# PowerBord.net
KiCad netlist of a schematic drawn in Altium Designer
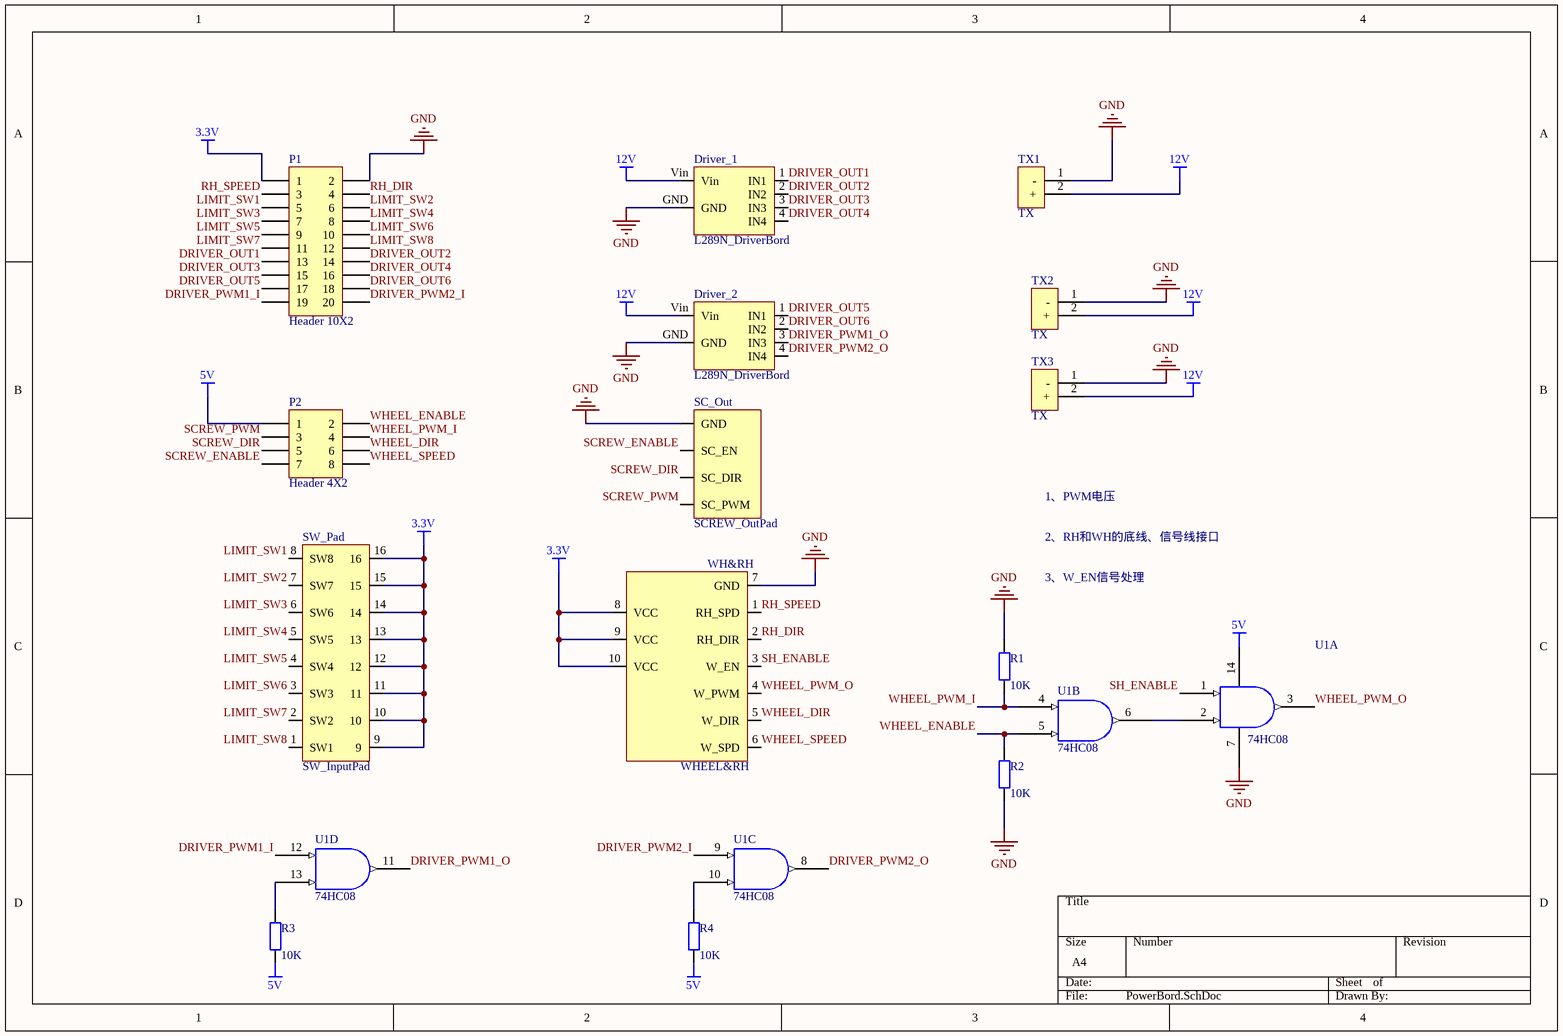
[diagram p0: PowerBord.SchDoc]

(export (version "E")
  (design (tool "Eeschema 10.0.6"))
  (components
    (comp (ref "Driver_1")
      (value "L289N_DriverBord")
      (footprint "L298N_DB")
      (libsource (lib "myLib") (part "L289N_DriverBord"))
    )
    (comp (ref "Driver_2")
      (value "L289N_DriverBord")
      (footprint "L298N_DB")
      (libsource (lib "myLib") (part "L289N_DriverBord"))
    )
    (comp (ref "P1")
      (value "Header 10X2")
      (footprint "JTAG20")
      (description "Header, 10-Pin, Dual row")
      (fields (field (name "PUBLISHER") "Altium Limited"))
      (libsource (lib "Miscellaneous Connectors") (part "Header 10X2"))
    )
    (comp (ref "P2")
      (value "Header 4X2")
      (footprint "HDR2X4")
      (description "Header, 4-Pin, Dual row")
      (fields (field (name "PUBLISHER") "Altium Limited"))
      (libsource (lib "Miscellaneous Connectors") (part "Header 4X2"))
    )
    (comp (ref "R1")
      (value "10K")
      (footprint "R 0805_M")
      (description "Resistor")
      (fields (field (name "PUBLISHER") "Altium Limited"))
      (libsource (lib "Miscellaneous Devices") (part "Res2"))
    )
    (comp (ref "R2")
      (value "10K")
      (footprint "R 0805_M")
      (description "Resistor")
      (fields (field (name "PUBLISHER") "Altium Limited"))
      (libsource (lib "Miscellaneous Devices") (part "Res2"))
    )
    (comp (ref "R3")
      (value "10K")
      (footprint "R 0805_M")
      (description "Resistor")
      (fields (field (name "PUBLISHER") "Altium Limited"))
      (libsource (lib "Miscellaneous Devices") (part "Res2"))
    )
    (comp (ref "R4")
      (value "10K")
      (footprint "R 0805_M")
      (description "Resistor")
      (fields (field (name "PUBLISHER") "Altium Limited"))
      (libsource (lib "Miscellaneous Devices") (part "Res2"))
    )
    (comp (ref "SC_Out")
      (value "SCREW_OutPad")
      (footprint "SC_OutPad")
      (libsource (lib "myLib") (part "SCREW_OutPad"))
    )
    (comp (ref "SW_Pad")
      (value "SW_InputPad")
      (footprint "SW_InputPad")
      (libsource (lib "myLib") (part "SW_InputPad"))
    )
    (comp (ref "TX1") (value "TX") (footprint "TX") (libsource (lib "接头") (part "T型插头")))
    (comp (ref "TX2") (value "TX") (footprint "TX") (libsource (lib "接头") (part "T型插头")))
    (comp (ref "TX3") (value "TX") (footprint "TX") (libsource (lib "接头") (part "T型插头")))
    (comp (ref "U1") (value "74HC08") (footprint "SOP-14") (libsource (lib "逻辑门器件") (part "74HC08")))
    (comp (ref "WH&RH") (value "WHEEL&RH") (footprint "WHEEL&RH") (libsource (lib "myLib") (part "WHEEL&RH")))
  )
  (nets
    (net (code "1") (name "/DRIVER_OUT1") (class "Default")
      (node (ref "Driver_1") (pin "1") (pinfunction "IN1_1") (pintype "passive"))
      (node (ref "P1") (pin "13") (pinfunction "13_13") (pintype "passive"))
    )
    (net (code "2") (name "/DRIVER_OUT2") (class "Default")
      (node (ref "Driver_1") (pin "2") (pinfunction "IN2_2") (pintype "passive"))
      (node (ref "P1") (pin "14") (pinfunction "14_14") (pintype "passive"))
    )
    (net (code "3") (name "/DRIVER_OUT3") (class "Default")
      (node (ref "Driver_1") (pin "3") (pinfunction "IN3_3") (pintype "passive"))
      (node (ref "P1") (pin "15") (pinfunction "15_15") (pintype "passive"))
    )
    (net (code "4") (name "/DRIVER_OUT4") (class "Default")
      (node (ref "Driver_1") (pin "4") (pinfunction "IN4_4") (pintype "passive"))
      (node (ref "P1") (pin "16") (pinfunction "16_16") (pintype "passive"))
    )
    (net (code "5") (name "/DRIVER_OUT5") (class "Default")
      (node (ref "Driver_2") (pin "1") (pinfunction "IN1_1") (pintype "passive"))
      (node (ref "P1") (pin "17") (pinfunction "17_17") (pintype "passive"))
    )
    (net (code "6") (name "/DRIVER_OUT6") (class "Default")
      (node (ref "Driver_2") (pin "2") (pinfunction "IN2_2") (pintype "passive"))
      (node (ref "P1") (pin "18") (pinfunction "18_18") (pintype "passive"))
    )
    (net (code "7") (name "/DRIVER_PWM1_I") (class "Default")
      (node (ref "P1") (pin "19") (pinfunction "19_19") (pintype "passive"))
      (node (ref "U1") (pin "12") (pintype "input"))
    )
    (net (code "8") (name "/DRIVER_PWM1_O") (class "Default")
      (node (ref "Driver_2") (pin "3") (pinfunction "IN3_3") (pintype "passive"))
      (node (ref "U1") (pin "11") (pintype "output"))
    )
    (net (code "9") (name "/DRIVER_PWM2_I") (class "Default")
      (node (ref "P1") (pin "20") (pinfunction "20_20") (pintype "passive"))
      (node (ref "U1") (pin "9") (pintype "input"))
    )
    (net (code "10") (name "/DRIVER_PWM2_O") (class "Default")
      (node (ref "Driver_2") (pin "4") (pinfunction "IN4_4") (pintype "passive"))
      (node (ref "U1") (pin "8") (pintype "output"))
    )
    (net (code "11") (name "/LIMIT_SW1") (class "Default")
      (node (ref "P1") (pin "5") (pinfunction "5_5") (pintype "passive"))
      (node (ref "SW_Pad") (pin "8") (pinfunction "SW8_8") (pintype "passive"))
    )
    (net (code "12") (name "/LIMIT_SW2") (class "Default")
      (node (ref "P1") (pin "6") (pinfunction "6_6") (pintype "passive"))
      (node (ref "SW_Pad") (pin "7") (pinfunction "SW7_7") (pintype "passive"))
    )
    (net (code "13") (name "/LIMIT_SW3") (class "Default")
      (node (ref "P1") (pin "7") (pinfunction "7_7") (pintype "passive"))
      (node (ref "SW_Pad") (pin "6") (pinfunction "SW6_6") (pintype "passive"))
    )
    (net (code "14") (name "/LIMIT_SW4") (class "Default")
      (node (ref "P1") (pin "8") (pinfunction "8_8") (pintype "passive"))
      (node (ref "SW_Pad") (pin "5") (pinfunction "SW5_5") (pintype "passive"))
    )
    (net (code "15") (name "/LIMIT_SW5") (class "Default")
      (node (ref "P1") (pin "9") (pinfunction "9_9") (pintype "passive"))
      (node (ref "SW_Pad") (pin "4") (pinfunction "SW4_4") (pintype "passive"))
    )
    (net (code "16") (name "/LIMIT_SW6") (class "Default")
      (node (ref "P1") (pin "10") (pinfunction "10_10") (pintype "passive"))
      (node (ref "SW_Pad") (pin "3") (pinfunction "SW3_3") (pintype "passive"))
    )
    (net (code "17") (name "/LIMIT_SW7") (class "Default")
      (node (ref "P1") (pin "11") (pinfunction "11_11") (pintype "passive"))
      (node (ref "SW_Pad") (pin "2") (pinfunction "SW2_2") (pintype "passive"))
    )
    (net (code "18") (name "/LIMIT_SW8") (class "Default")
      (node (ref "P1") (pin "12") (pinfunction "12_12") (pintype "passive"))
      (node (ref "SW_Pad") (pin "1") (pinfunction "SW1_1") (pintype "passive"))
    )
    (net (code "19") (name "/RH_DIR") (class "Default")
      (node (ref "P1") (pin "4") (pinfunction "4_4") (pintype "passive"))
      (node (ref "WH&RH") (pin "2") (pinfunction "RH_DIR_2") (pintype "passive"))
    )
    (net (code "20") (name "/RH_SPEED") (class "Default")
      (node (ref "P1") (pin "3") (pinfunction "3_3") (pintype "passive"))
      (node (ref "WH&RH") (pin "1") (pinfunction "RH_SPD_1") (pintype "passive"))
    )
    (net (code "21") (name "/SCREW_DIR") (class "Default")
      (node (ref "P2") (pin "5") (pinfunction "5_5") (pintype "passive"))
      (node (ref "SC_Out") (pin "2") (pinfunction "SC_DIR_2") (pintype "passive"))
    )
    (net (code "22") (name "/SCREW_ENABLE") (class "Default")
      (node (ref "P2") (pin "7") (pinfunction "7_7") (pintype "passive"))
      (node (ref "SC_Out") (pin "3") (pinfunction "SC_EN_3") (pintype "passive"))
    )
    (net (code "23") (name "/SCREW_PWM") (class "Default")
      (node (ref "P2") (pin "3") (pinfunction "3_3") (pintype "passive"))
      (node (ref "SC_Out") (pin "1") (pinfunction "SC_PWM_1") (pintype "passive"))
    )
    (net (code "24") (name "/SH_ENABLE") (class "Default")
      (node (ref "U1") (pin "1") (pintype "input"))
      (node (ref "WH&RH") (pin "3") (pinfunction "W_EN_3") (pintype "passive"))
    )
    (net (code "25") (name "/WHEEL_DIR") (class "Default")
      (node (ref "P2") (pin "6") (pinfunction "6_6") (pintype "passive"))
      (node (ref "WH&RH") (pin "5") (pinfunction "W_DIR_5") (pintype "passive"))
    )
    (net (code "26") (name "/WHEEL_ENABLE") (class "Default")
      (node (ref "P2") (pin "2") (pinfunction "2_2") (pintype "passive"))
      (node (ref "R2") (pin "2") (pinfunction "2_2") (pintype "passive"))
      (node (ref "U1") (pin "5") (pintype "input"))
    )
    (net (code "27") (name "/WHEEL_PWM_I") (class "Default")
      (node (ref "P2") (pin "4") (pinfunction "4_4") (pintype "passive"))
      (node (ref "R1") (pin "1") (pinfunction "1_1") (pintype "passive"))
      (node (ref "U1") (pin "4") (pintype "input"))
    )
    (net (code "28") (name "/WHEEL_PWM_O") (class "Default")
      (node (ref "U1") (pin "3") (pintype "output"))
      (node (ref "WH&RH") (pin "4") (pinfunction "W_PWM_4") (pintype "passive"))
    )
    (net (code "29") (name "/WHEEL_SPEED") (class "Default")
      (node (ref "P2") (pin "8") (pinfunction "8_8") (pintype "passive"))
      (node (ref "WH&RH") (pin "6") (pinfunction "W_SPD_6") (pintype "passive"))
    )
    (net (code "30") (name "3.3V") (class "Default")
      (node (ref "P1") (pin "1") (pinfunction "1_1") (pintype "passive"))
      (node (ref "SW_Pad") (pin "10") (pinfunction "10_10") (pintype "passive"))
      (node (ref "SW_Pad") (pin "11") (pinfunction "11_11") (pintype "passive"))
      (node (ref "SW_Pad") (pin "12") (pinfunction "12_12") (pintype "passive"))
      (node (ref "SW_Pad") (pin "13") (pinfunction "13_13") (pintype "passive"))
      (node (ref "SW_Pad") (pin "14") (pinfunction "14_14") (pintype "passive"))
      (node (ref "SW_Pad") (pin "15") (pinfunction "15_15") (pintype "passive"))
      (node (ref "SW_Pad") (pin "16") (pinfunction "16_16") (pintype "passive"))
      (node (ref "SW_Pad") (pin "9") (pinfunction "9_9") (pintype "passive"))
      (node (ref "WH&RH") (pin "10") (pinfunction "VCC_10") (pintype "passive"))
      (node (ref "WH&RH") (pin "8") (pinfunction "VCC_8") (pintype "passive"))
      (node (ref "WH&RH") (pin "9") (pinfunction "VCC_9") (pintype "passive"))
    )
    (net (code "31") (name "5V") (class "Default")
      (node (ref "P2") (pin "1") (pinfunction "1_1") (pintype "passive"))
      (node (ref "R3") (pin "1") (pinfunction "1_1") (pintype "passive"))
      (node (ref "R4") (pin "1") (pinfunction "1_1") (pintype "passive"))
      (node (ref "U1") (pin "14") (pinfunction "VCC_14") (pintype "power_in"))
    )
    (net (code "32") (name "12V") (class "Default")
      (node (ref "Driver_1") (pin "Vin") (pinfunction "Vin_Vin") (pintype "passive"))
      (node (ref "Driver_2") (pin "Vin") (pinfunction "Vin_Vin") (pintype "passive"))
      (node (ref "TX1") (pin "2") (pinfunction "+_2") (pintype "passive"))
      (node (ref "TX2") (pin "2") (pinfunction "+_2") (pintype "passive"))
      (node (ref "TX3") (pin "2") (pinfunction "+_2") (pintype "passive"))
    )
    (net (code "33") (name "GND") (class "Default")
      (node (ref "Driver_1") (pin "GND") (pinfunction "GND_GND") (pintype "passive"))
      (node (ref "Driver_2") (pin "GND") (pinfunction "GND_GND") (pintype "passive"))
      (node (ref "P1") (pin "2") (pinfunction "2_2") (pintype "passive"))
      (node (ref "R1") (pin "2") (pinfunction "2_2") (pintype "passive"))
      (node (ref "R2") (pin "1") (pinfunction "1_1") (pintype "passive"))
      (node (ref "SC_Out") (pin "4") (pinfunction "GND_4") (pintype "passive"))
      (node (ref "TX1") (pin "1") (pinfunction "-_1") (pintype "passive"))
      (node (ref "TX2") (pin "1") (pinfunction "-_1") (pintype "passive"))
      (node (ref "TX3") (pin "1") (pinfunction "-_1") (pintype "passive"))
      (node (ref "U1") (pin "7") (pinfunction "GND_7") (pintype "power_in"))
      (node (ref "WH&RH") (pin "7") (pinfunction "GND_7") (pintype "passive"))
    )
    (net (code "34") (name "Net-(R3-Pad2)") (class "Default")
      (node (ref "R3") (pin "2") (pinfunction "2_2") (pintype "passive"))
      (node (ref "U1") (pin "13") (pintype "input"))
    )
    (net (code "35") (name "Net-(R4-Pad2)") (class "Default")
      (node (ref "R4") (pin "2") (pinfunction "2_2") (pintype "passive"))
      (node (ref "U1") (pin "10") (pintype "input"))
    )
    (net (code "36") (name "Net-(U1-Pad2)") (class "Default")
      (node (ref "U1") (pin "2") (pintype "input"))
      (node (ref "U1") (pin "6") (pintype "output"))
    )
  )
)
